# Experiment_3_0_0_0.net
KiCad netlist of a schematic drawn in Altium Designer
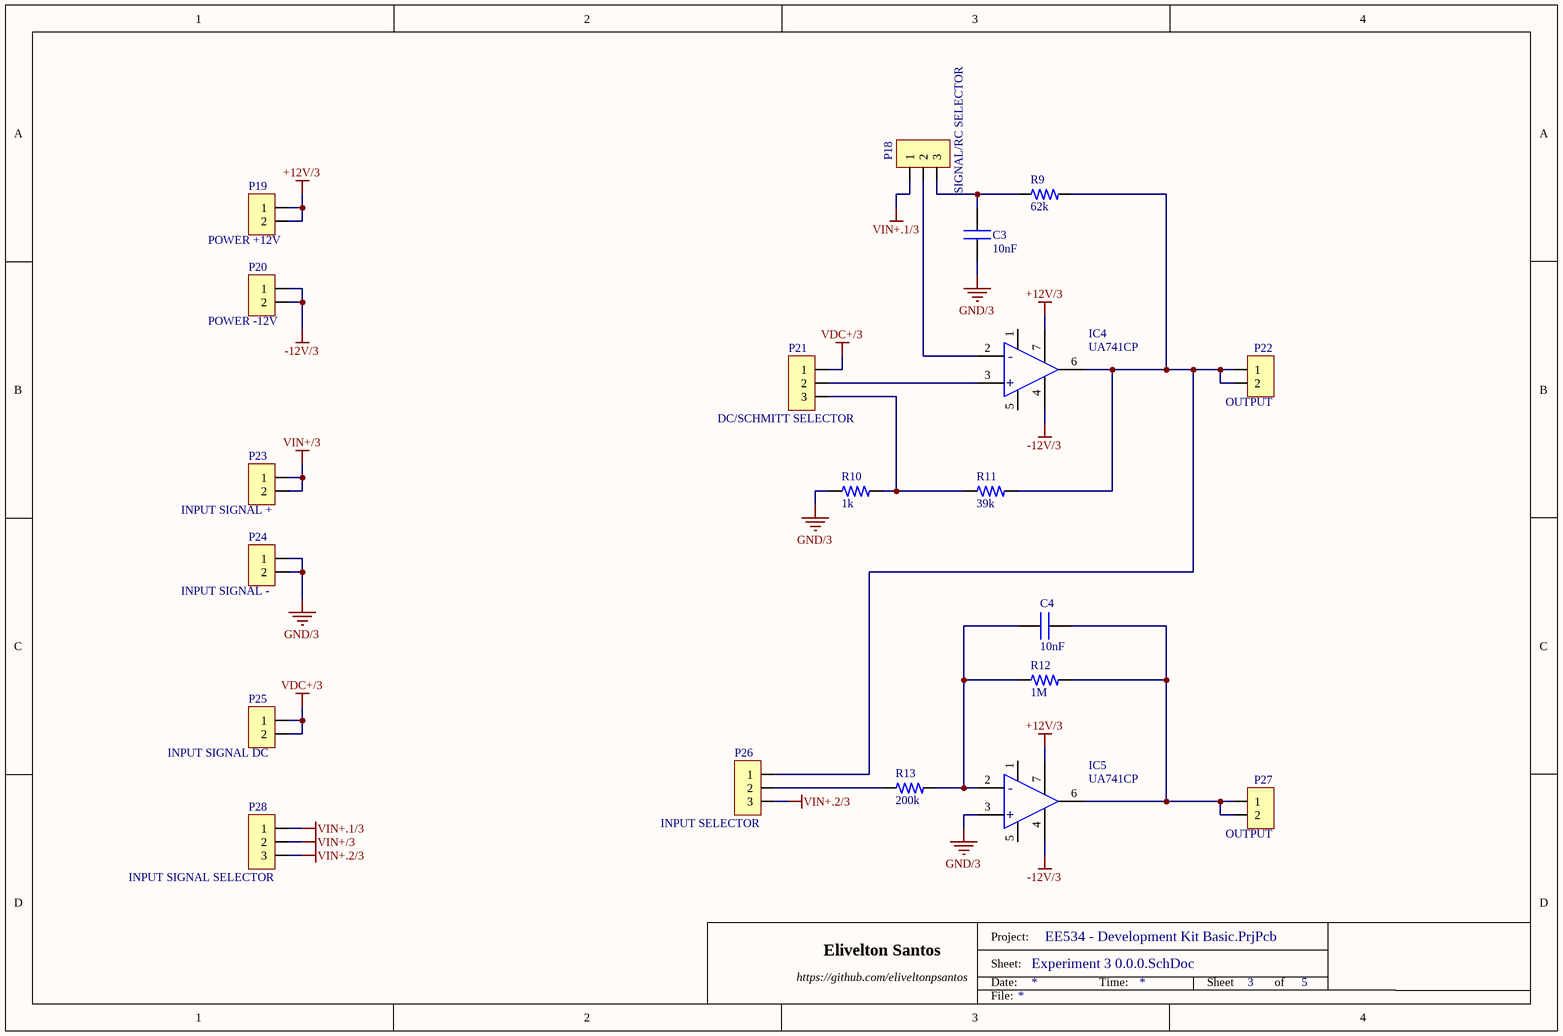
[diagram p0: Experiment 3 0.0.0.SchDoc]

(export (version "E")
  (design (tool "Eeschema 10.0.6"))
  (components
    (comp (ref "C3")
      (value "10nF")
      (footprint "CAP-H5")
      (description "CAP CER 10000PF 50V X7R RADIAL")
      (fields
        (field (name "MANUFACTURER") "Vishay BC Components")
        (field (name "MANUFACTURER PART NUMBER") "K101K10X7RF5UH5")
      )
      (libsource (lib "Capacitors") (part "K103K10X7RF5UH5"))
    )
    (comp (ref "C4")
      (value "10nF")
      (footprint "CAP-H5")
      (description "CAP CER 10000PF 50V X7R RADIAL")
      (fields
        (field (name "MANUFACTURER") "Vishay BC Components")
        (field (name "MANUFACTURER PART NUMBER") "K101K10X7RF5UH5")
      )
      (libsource (lib "Capacitors") (part "K103K10X7RF5UH5"))
    )
    (comp (ref "IC4")
      (value "UA741CP")
      (footprint "DIP-8")
      (description "IC OPAMP GP 1MHZ 8DIP")
      (fields (field (name "MANUFACTURER") "Texas Instruments"))
      (libsource (lib "ICs") (part "UA741CP"))
    )
    (comp (ref "IC5")
      (value "UA741CP")
      (footprint "DIP-8")
      (description "IC OPAMP GP 1MHZ 8DIP")
      (fields (field (name "MANUFACTURER") "Texas Instruments"))
      (libsource (lib "ICs") (part "UA741CP"))
    )
    (comp (ref "P18")
      (value "SIGNAL/RC SELECTOR")
      (footprint "PINHD-1X03")
      (description "CONN HEADER 3POS .100\" STR TIN")
      (fields
        (field (name "MANUFACTURER") "Molex, LLC")
        (field (name "MANUFACTURER PART NUMBER") "0901200123")
      )
      (libsource (lib "") (part "PIN HEADER 1X03_1"))
    )
    (comp (ref "P19")
      (value "POWER +12V")
      (footprint "PINHD-1X02 ONCE")
      (description "CONN HEADER 2POS .100\" STR TIN")
      (fields
        (field (name "MANUFACTURER") "Molex, LLC")
        (field (name "MANUFACTURER PART NUMBER") "0901200122")
      )
      (libsource (lib "") (part "PIN HEADER 1X02 ONCE_1"))
    )
    (comp (ref "P20")
      (value "POWER -12V")
      (footprint "PINHD-1X02 ONCE")
      (description "CONN HEADER 2POS .100\" STR TIN")
      (fields
        (field (name "MANUFACTURER") "Molex, LLC")
        (field (name "MANUFACTURER PART NUMBER") "0901200122")
      )
      (libsource (lib "") (part "PIN HEADER 1X02 ONCE_1"))
    )
    (comp (ref "P21")
      (value "DC/SCHMITT SELECTOR")
      (footprint "PINHD-1X03")
      (description "CONN HEADER 3POS .100\" STR TIN")
      (fields
        (field (name "MANUFACTURER") "Molex, LLC")
        (field (name "MANUFACTURER PART NUMBER") "0901200123")
      )
      (libsource (lib "Connectors") (part "PIN HEADER 1X03"))
    )
    (comp (ref "P22")
      (value "OUTPUT")
      (footprint "PINHD-1X02 ONCE")
      (description "CONN HEADER 2POS .100\" STR TIN")
      (fields
        (field (name "MANUFACTURER") "Molex, LLC")
        (field (name "MANUFACTURER PART NUMBER") "0901200122")
      )
      (libsource (lib "Connectors") (part "PIN HEADER 1X02 ONCE"))
    )
    (comp (ref "P23")
      (value "INPUT SIGNAL +")
      (footprint "PINHD-1X02 ONCE")
      (description "CONN HEADER 2POS .100\" STR TIN")
      (fields
        (field (name "MANUFACTURER") "Molex, LLC")
        (field (name "MANUFACTURER PART NUMBER") "0901200122")
      )
      (libsource (lib "") (part "PIN HEADER 1X02 ONCE_1"))
    )
    (comp (ref "P24")
      (value "INPUT SIGNAL -")
      (footprint "PINHD-1X02 ONCE")
      (description "CONN HEADER 2POS .100\" STR TIN")
      (fields
        (field (name "MANUFACTURER") "Molex, LLC")
        (field (name "MANUFACTURER PART NUMBER") "0901200122")
      )
      (libsource (lib "") (part "PIN HEADER 1X02 ONCE_1"))
    )
    (comp (ref "P25")
      (value "INPUT SIGNAL DC")
      (footprint "PINHD-1X02 ONCE")
      (description "CONN HEADER 2POS .100\" STR TIN")
      (fields
        (field (name "MANUFACTURER") "Molex, LLC")
        (field (name "MANUFACTURER PART NUMBER") "0901200122")
      )
      (libsource (lib "") (part "PIN HEADER 1X02 ONCE_1"))
    )
    (comp (ref "P26")
      (value "INPUT SELECTOR")
      (footprint "PINHD-1X03")
      (description "CONN HEADER 3POS .100\" STR TIN")
      (fields
        (field (name "MANUFACTURER") "Molex, LLC")
        (field (name "MANUFACTURER PART NUMBER") "0901200123")
      )
      (libsource (lib "Connectors") (part "PIN HEADER 1X03"))
    )
    (comp (ref "P27")
      (value "OUTPUT")
      (footprint "PINHD-1X02 ONCE")
      (description "CONN HEADER 2POS .100\" STR TIN")
      (fields
        (field (name "MANUFACTURER") "Molex, LLC")
        (field (name "MANUFACTURER PART NUMBER") "0901200122")
      )
      (libsource (lib "Connectors") (part "PIN HEADER 1X02 ONCE"))
    )
    (comp (ref "P28")
      (value "INPUT SIGNAL SELECTOR")
      (footprint "PINHD-1X03")
      (description "CONN HEADER 3POS .100\" STR TIN")
      (fields
        (field (name "MANUFACTURER") "Molex, LLC")
        (field (name "MANUFACTURER PART NUMBER") "0901200123")
      )
      (libsource (lib "Connectors") (part "PIN HEADER 1X03"))
    )
    (comp (ref "R9")
      (value "62k")
      (footprint "R Axial 0.25")
      (description "RES 62K OHM 1/4W 5% AXIAL")
      (fields
        (field (name "MANUFACTURER") "Yageo")
        (field (name "MANUFACTURER PART NUMBER") "CFR-25JB-52-62K")
      )
      (libsource (lib "Resistors") (part "CFR-25JB-52-62K"))
    )
    (comp (ref "R10")
      (value "1k")
      (footprint "R Axial 0.25")
      (description "RES 1K OHM 1/4W 5% AXIAL")
      (fields
        (field (name "MANUFACTURER") "Yageo")
        (field (name "MANUFACTURER PART NUMBER") "CFR-25JB-52-1K")
      )
      (libsource (lib "Resistors") (part "CFR-25JB-52-1K"))
    )
    (comp (ref "R11")
      (value "39k")
      (footprint "R Axial 0.25")
      (description "RES 39K OHM 1/4W 5% AXIAL")
      (fields
        (field (name "MANUFACTURER") "Yageo")
        (field (name "MANUFACTURER PART NUMBER") "CFR-25JB-52-39K")
      )
      (libsource (lib "Resistors") (part "CFR-25JB-52-39K"))
    )
    (comp (ref "R12")
      (value "1M")
      (footprint "R Axial 0.25")
      (description "RES 1M OHM 1/4W 5% AXIAL")
      (fields
        (field (name "MANUFACTURER") "Yageo")
        (field (name "MANUFACTURER PART NUMBER") "CFR-25JB-52-1M")
      )
      (libsource (lib "Resistors") (part "CFR-25JB-52-1M"))
    )
    (comp (ref "R13")
      (value "200k")
      (footprint "R Axial 0.25")
      (description "RES 200K OHM 1/4W 5% AXIAL")
      (fields
        (field (name "MANUFACTURER") "Yageo")
        (field (name "MANUFACTURER PART NUMBER") "CFR-25JB-52-200K")
      )
      (libsource (lib "Resistors") (part "CFR-25JB-52-200K"))
    )
  )
  (nets
    (net (code "1") (name "+12V{slash}3") (class "Default")
      (node (ref "IC4") (pin "7") (pinfunction "VCC+_7") (pintype "power_in"))
      (node (ref "IC5") (pin "7") (pinfunction "VCC+_7") (pintype "power_in"))
      (node (ref "P19") (pin "1") (pinfunction "1_1") (pintype "passive"))
      (node (ref "P19") (pin "2") (pinfunction "2_2") (pintype "passive"))
    )
    (net (code "2") (name "-12V{slash}3") (class "Default")
      (node (ref "IC4") (pin "4") (pinfunction "VCC-_4") (pintype "power_in"))
      (node (ref "IC5") (pin "4") (pinfunction "VCC-_4") (pintype "power_in"))
      (node (ref "P20") (pin "1") (pinfunction "1_1") (pintype "passive"))
      (node (ref "P20") (pin "2") (pinfunction "2_2") (pintype "passive"))
    )
    (net (code "3") (name "GND{slash}3") (class "Default")
      (node (ref "C3") (pin "1") (pinfunction "1_1") (pintype "passive"))
      (node (ref "IC5") (pin "3") (pinfunction "+_3") (pintype "passive"))
      (node (ref "P24") (pin "1") (pinfunction "1_1") (pintype "passive"))
      (node (ref "P24") (pin "2") (pinfunction "2_2") (pintype "passive"))
      (node (ref "R10") (pin "1") (pinfunction "1_1") (pintype "passive"))
    )
    (net (code "4") (name "Net-(C3-Pad2)") (class "Default")
      (node (ref "C3") (pin "2") (pinfunction "2_2") (pintype "passive"))
      (node (ref "P18") (pin "3") (pinfunction "3_3") (pintype "passive"))
      (node (ref "R9") (pin "1") (pinfunction "1_1") (pintype "passive"))
    )
    (net (code "5") (name "Net-(IC4-+)") (class "Default")
      (node (ref "IC4") (pin "3") (pinfunction "+_3") (pintype "passive"))
      (node (ref "P21") (pin "2") (pinfunction "2_2") (pintype "passive"))
    )
    (net (code "6") (name "Net-(IC4--)") (class "Default")
      (node (ref "IC4") (pin "2") (pinfunction "-_2") (pintype "passive"))
      (node (ref "P18") (pin "2") (pinfunction "2_2") (pintype "passive"))
    )
    (net (code "7") (name "Net-(IC4-OUTPUT)") (class "Default")
      (node (ref "IC4") (pin "6") (pinfunction "OUTPUT_6") (pintype "passive"))
      (node (ref "P22") (pin "1") (pinfunction "1_1") (pintype "passive"))
      (node (ref "P22") (pin "2") (pinfunction "2_2") (pintype "passive"))
      (node (ref "P26") (pin "1") (pinfunction "1_1") (pintype "passive"))
      (node (ref "R11") (pin "2") (pinfunction "2_2") (pintype "passive"))
      (node (ref "R9") (pin "2") (pinfunction "2_2") (pintype "passive"))
    )
    (net (code "8") (name "Net-(IC5--)") (class "Default")
      (node (ref "C4") (pin "2") (pinfunction "2_2") (pintype "passive"))
      (node (ref "IC5") (pin "2") (pinfunction "-_2") (pintype "passive"))
      (node (ref "R12") (pin "1") (pinfunction "1_1") (pintype "passive"))
      (node (ref "R13") (pin "2") (pinfunction "2_2") (pintype "passive"))
    )
    (net (code "9") (name "Net-(IC5-OUTPUT)") (class "Default")
      (node (ref "C4") (pin "1") (pinfunction "1_1") (pintype "passive"))
      (node (ref "IC5") (pin "6") (pinfunction "OUTPUT_6") (pintype "passive"))
      (node (ref "P27") (pin "1") (pinfunction "1_1") (pintype "passive"))
      (node (ref "P27") (pin "2") (pinfunction "2_2") (pintype "passive"))
      (node (ref "R12") (pin "2") (pinfunction "2_2") (pintype "passive"))
    )
    (net (code "10") (name "Net-(P21-Pad3)") (class "Default")
      (node (ref "P21") (pin "3") (pinfunction "3_3") (pintype "passive"))
      (node (ref "R10") (pin "2") (pinfunction "2_2") (pintype "passive"))
      (node (ref "R11") (pin "1") (pinfunction "1_1") (pintype "passive"))
    )
    (net (code "11") (name "Net-(P26-Pad2)") (class "Default")
      (node (ref "P26") (pin "2") (pinfunction "2_2") (pintype "passive"))
      (node (ref "R13") (pin "1") (pinfunction "1_1") (pintype "passive"))
    )
    (net (code "12") (name "VDC+{slash}3") (class "Default")
      (node (ref "P21") (pin "1") (pinfunction "1_1") (pintype "passive"))
      (node (ref "P25") (pin "1") (pinfunction "1_1") (pintype "passive"))
      (node (ref "P25") (pin "2") (pinfunction "2_2") (pintype "passive"))
    )
    (net (code "13") (name "VIN+.1{slash}3") (class "Default")
      (node (ref "P18") (pin "1") (pinfunction "1_1") (pintype "passive"))
      (node (ref "P28") (pin "1") (pinfunction "1_1") (pintype "passive"))
    )
    (net (code "14") (name "VIN+.2{slash}3") (class "Default")
      (node (ref "P26") (pin "3") (pinfunction "3_3") (pintype "passive"))
      (node (ref "P28") (pin "3") (pinfunction "3_3") (pintype "passive"))
    )
    (net (code "15") (name "VIN+{slash}3") (class "Default")
      (node (ref "P23") (pin "1") (pinfunction "1_1") (pintype "passive"))
      (node (ref "P23") (pin "2") (pinfunction "2_2") (pintype "passive"))
      (node (ref "P28") (pin "2") (pinfunction "2_2") (pintype "passive"))
    )
    (net (code "16") (name "unconnected-(IC4-OFFSET1-Pad1)") (class "Default")
      (node (ref "IC4") (pin "1") (pinfunction "OFFSET1_1") (pintype "passive"))
    )
    (net (code "17") (name "unconnected-(IC4-OFFSET2-Pad5)") (class "Default")
      (node (ref "IC4") (pin "5") (pinfunction "OFFSET2_5") (pintype "passive"))
    )
    (net (code "18") (name "unconnected-(IC5-OFFSET1-Pad1)") (class "Default")
      (node (ref "IC5") (pin "1") (pinfunction "OFFSET1_1") (pintype "passive"))
    )
    (net (code "19") (name "unconnected-(IC5-OFFSET2-Pad5)") (class "Default")
      (node (ref "IC5") (pin "5") (pinfunction "OFFSET2_5") (pintype "passive"))
    )
  )
)
